# main.net
KiCad netlist of a schematic drawn in Altium Designer
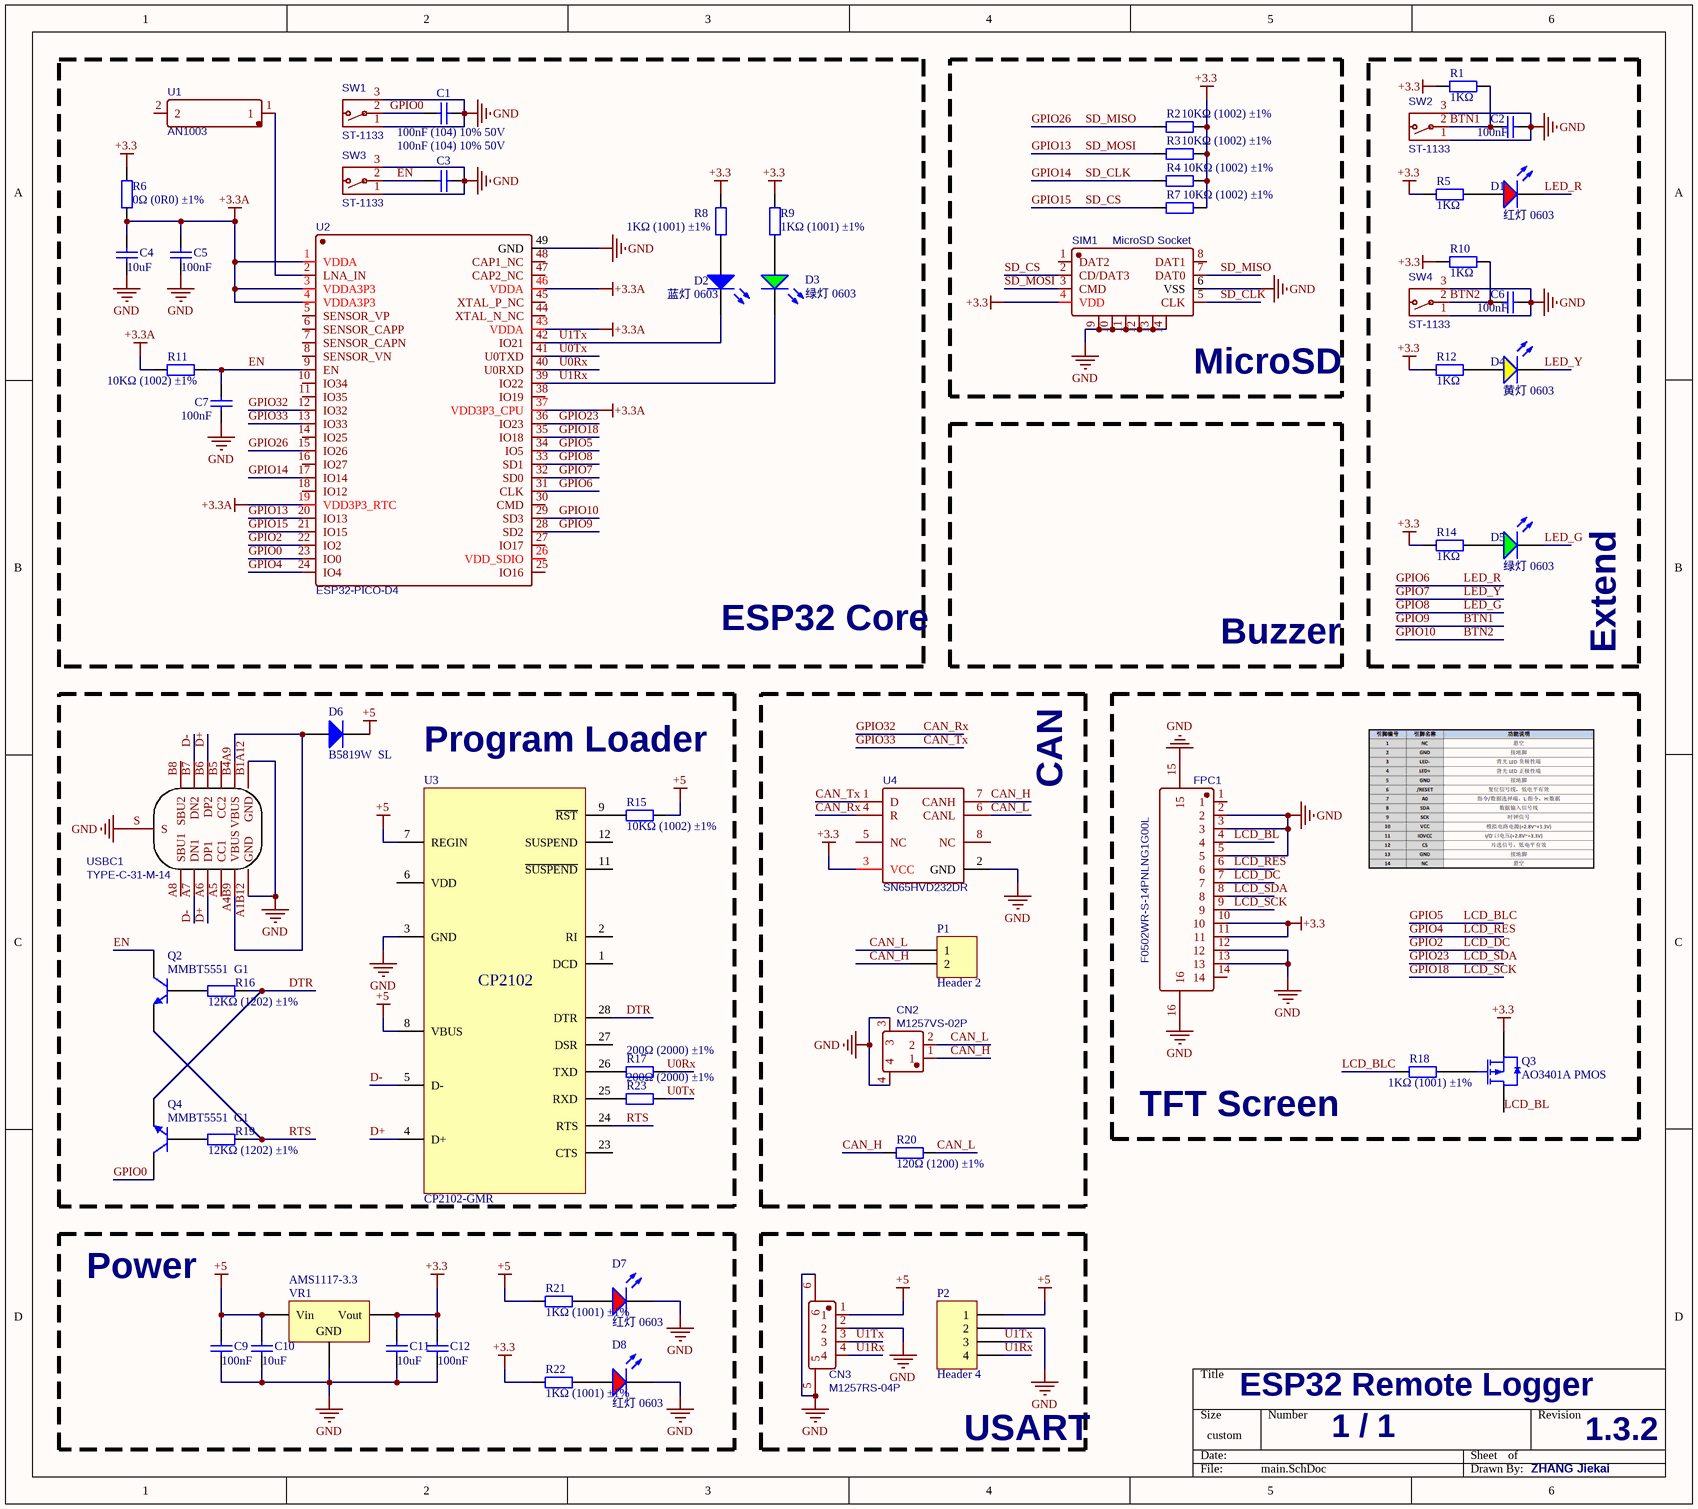
[diagram p0: main.SchDoc]

(export (version "E")
  (design (tool "Eeschema 10.0.6"))
  (components
    (comp (ref "C1")
      (value "100nF (104) 10% 50V")
      (footprint "0603_C")
      (description "贴片电容")
      (libsource (lib "Miscellaneous Devices LC") (part "0603 100nF (104) 10% 50V"))
    )
    (comp (ref "C2")
      (value "100nF")
      (footprint "0603_C")
      (description "贴片电容")
      (libsource (lib "Miscellaneous Devices LC") (part "0603 100nF (104) 10% 50V"))
    )
    (comp (ref "C3")
      (value "100nF (104) 10% 50V")
      (footprint "0603_C")
      (description "贴片电容")
      (libsource (lib "Miscellaneous Devices LC") (part "0603 100nF (104) 10% 50V"))
    )
    (comp (ref "C4")
      (value "10uF")
      (footprint "0603_C")
      (description "贴片电容")
      (libsource (lib "Miscellaneous Devices LC") (part "0603 10uF (106) 10% 10V"))
    )
    (comp (ref "C5")
      (value "100nF")
      (footprint "0603_C")
      (description "贴片电容")
      (libsource (lib "Miscellaneous Devices LC") (part "0603 100nF (104) 10% 50V"))
    )
    (comp (ref "C6")
      (value "100nF")
      (footprint "0603_C")
      (description "贴片电容")
      (libsource (lib "Miscellaneous Devices LC") (part "0603 100nF (104) 10% 50V"))
    )
    (comp (ref "C7")
      (value "100nF")
      (footprint "0603_C")
      (description "贴片电容")
      (libsource (lib "Miscellaneous Devices LC") (part "0603 100nF (104) 10% 50V"))
    )
    (comp (ref "C9")
      (value "100nF")
      (footprint "0603_C")
      (description "贴片电容")
      (libsource (lib "Miscellaneous Devices LC") (part "0603 100nF (104) 10% 50V"))
    )
    (comp (ref "C10")
      (value "10uF")
      (footprint "0603_C")
      (description "贴片电容")
      (libsource (lib "Miscellaneous Devices LC") (part "0603 10uF (106) 10% 10V"))
    )
    (comp (ref "C11")
      (value "10uF")
      (footprint "0603_C")
      (description "贴片电容")
      (libsource (lib "Miscellaneous Devices LC") (part "0603 10uF (106) 10% 10V"))
    )
    (comp (ref "C12")
      (value "100nF")
      (footprint "0603_C")
      (description "贴片电容")
      (libsource (lib "Miscellaneous Devices LC") (part "0603 100nF (104) 10% 50V"))
    )
    (comp (ref "CN2")
      (value "M1257VS-02P")
      (footprint "CONN-SMD_P1.25_M1257VS-02P")
      (fields (field (name "BOM_SUPPLIER PART") "C541819") (field (name "CONTRIBUTOR") "LCSC"))
      (libsource (lib "GH2P_Stand") (part "M1257VS-02P"))
    )
    (comp (ref "CN3")
      (value "M1257RS-04P")
      (footprint "CONN-SMD_M1257RS-04P")
      (fields (field (name "BOM_SUPPLIER PART") "C541828") (field (name "CONTRIBUTOR") "LCSC"))
      (libsource (lib "GH-lay-4P") (part "M1257RS-04P"))
    )
    (comp (ref "D1")
      (value "红灯 0603")
      (footprint "0603_LED_S1")
      (description "发光二极管")
      (libsource (lib "Miscellaneous Devices LC") (part "0603 红灯"))
    )
    (comp (ref "D2")
      (value "蓝灯 0603")
      (footprint "0603_LED_S1")
      (description "发光二极管")
      (libsource (lib "Miscellaneous Devices LC") (part "0603 蓝灯"))
    )
    (comp (ref "D3")
      (value "绿灯 0603")
      (footprint "0603_LED_S1")
      (description "发光二极管")
      (libsource (lib "Miscellaneous Devices LC") (part "0603 绿灯"))
    )
    (comp (ref "D4")
      (value "黄灯 0603")
      (footprint "0603_LED_S1")
      (description "发光二极管")
      (libsource (lib "Miscellaneous Devices LC") (part "0603 黄灯"))
    )
    (comp (ref "D5")
      (value "绿灯 0603")
      (footprint "0603_LED_S1")
      (description "发光二极管")
      (libsource (lib "Miscellaneous Devices LC") (part "0603 绿灯"))
    )
    (comp (ref "D6")
      (value "B5819W  SL")
      (footprint "SOD-123")
      (description "肖特基二极管")
      (libsource (lib "Miscellaneous Devices LC") (part "SOD-123 B5819W  SL"))
    )
    (comp (ref "D7")
      (value "红灯 0603")
      (footprint "0603_LED_S1")
      (description "发光二极管")
      (libsource (lib "Miscellaneous Devices LC") (part "0603 红灯"))
    )
    (comp (ref "D8")
      (value "红灯 0603")
      (footprint "0603_LED_S1")
      (description "发光二极管")
      (libsource (lib "Miscellaneous Devices LC") (part "0603 红灯"))
    )
    (comp (ref "FPC1")
      (value "F0502WR-S-14PNLNG1G00L")
      (footprint "FPC-SMD_P0.50-14P_F0500WR-S")
      (fields (field (name "BOM_SUPPLIER PART") "C247902") (field (name "CONTRIBUTOR") "LCSC"))
      (libsource (lib "14P-FFC-Connector") (part "F0502WR-S-14PNLNG1G00L"))
    )
    (comp (ref "P1")
      (value "Header 2")
      (footprint "HDR1X2")
      (description "Header, 2-Pin")
      (fields (field (name "PUBLISHER") "Altium Limited"))
      (libsource (lib "Miscellaneous Connectors") (part "Header 2"))
    )
    (comp (ref "P2")
      (value "Header 4")
      (footprint "HDR1X4")
      (description "Header, 4-Pin")
      (fields (field (name "PUBLISHER") "Altium Limited"))
      (libsource (lib "Miscellaneous Connectors") (part "Header 4"))
    )
    (comp (ref "Q2")
      (value "MMBT5551  G1")
      (footprint "SOT-23(SOT-23-3)")
      (description "三极管")
      (libsource (lib "Miscellaneous Devices LC") (part "SOT-23 MMBT5551  G1"))
    )
    (comp (ref "Q3")
      (value "AO3401A PMOS")
      (footprint "SOT-23-3L")
      (description "MOS(场效应管)")
      (libsource (lib "Miscellaneous Devices LC") (part "AO3401A P道沟 X13A15 SOT-23"))
    )
    (comp (ref "Q4")
      (value "MMBT5551  G1")
      (footprint "SOT-23(SOT-23-3)")
      (description "三极管")
      (libsource (lib "Miscellaneous Devices LC") (part "SOT-23 MMBT5551  G1"))
    )
    (comp (ref "R1")
      (value "1KΩ")
      (footprint "0603_R")
      (description "贴片电阻")
      (libsource (lib "Miscellaneous Devices LC") (part "0603 1KΩ (1001) 1%"))
    )
    (comp (ref "R2")
      (value "10KΩ (1002) ±1%")
      (footprint "0603_R")
      (description "贴片电阻")
      (libsource (lib "Miscellaneous Devices LC") (part "0603 10KΩ (1002) 1%"))
    )
    (comp (ref "R3")
      (value "10KΩ (1002) ±1%")
      (footprint "0603_R")
      (description "贴片电阻")
      (libsource (lib "Miscellaneous Devices LC") (part "0603 10KΩ (1002) 1%"))
    )
    (comp (ref "R4")
      (value "10KΩ (1002) ±1%")
      (footprint "0603_R")
      (description "贴片电阻")
      (libsource (lib "Miscellaneous Devices LC") (part "0603 10KΩ (1002) 1%"))
    )
    (comp (ref "R5")
      (value "1KΩ")
      (footprint "0603_R")
      (description "贴片电阻")
      (libsource (lib "Miscellaneous Devices LC") (part "0603 1KΩ (1001) 1%"))
    )
    (comp (ref "R6")
      (value "0Ω (0R0) ±1%")
      (footprint "0603_R")
      (description "贴片电阻")
      (libsource (lib "Miscellaneous Devices LC") (part "0603 0Ω (0R0) 1%"))
    )
    (comp (ref "R7")
      (value "10KΩ (1002) ±1%")
      (footprint "0603_R")
      (description "贴片电阻")
      (libsource (lib "Miscellaneous Devices LC") (part "0603 10KΩ (1002) 1%"))
    )
    (comp (ref "R8")
      (value "1KΩ (1001) ±1%")
      (footprint "0603_R")
      (description "贴片电阻")
      (libsource (lib "") (part "0603 1KΩ (1001) 1%_1"))
    )
    (comp (ref "R9")
      (value "1KΩ (1001) ±1%")
      (footprint "0603_R")
      (description "贴片电阻")
      (libsource (lib "") (part "0603 1KΩ (1001) 1%_1"))
    )
    (comp (ref "R10")
      (value "1KΩ")
      (footprint "0603_R")
      (description "贴片电阻")
      (libsource (lib "Miscellaneous Devices LC") (part "0603 1KΩ (1001) 1%"))
    )
    (comp (ref "R11")
      (value "10KΩ (1002) ±1%")
      (footprint "0603_R")
      (description "贴片电阻")
      (libsource (lib "Miscellaneous Devices LC") (part "0603 10KΩ (1002) 1%"))
    )
    (comp (ref "R12")
      (value "1KΩ")
      (footprint "0603_R")
      (description "贴片电阻")
      (libsource (lib "Miscellaneous Devices LC") (part "0603 1KΩ (1001) 1%"))
    )
    (comp (ref "R14")
      (value "1KΩ")
      (footprint "0603_R")
      (description "贴片电阻")
      (libsource (lib "Miscellaneous Devices LC") (part "0603 1KΩ (1001) 1%"))
    )
    (comp (ref "R15")
      (value "10KΩ (1002) ±1%")
      (footprint "0603_R")
      (description "贴片电阻")
      (libsource (lib "Miscellaneous Devices LC") (part "0603 10KΩ (1002) 1%"))
    )
    (comp (ref "R16")
      (value "12KΩ (1202) ±1%")
      (footprint "0603_R")
      (description "贴片电阻")
      (libsource (lib "Miscellaneous Devices LC") (part "0603 12KΩ (1202) 1%"))
    )
    (comp (ref "R17")
      (value "200Ω (2000) ±1%")
      (footprint "0603_R")
      (description "贴片电阻")
      (libsource (lib "Miscellaneous Devices LC") (part "0603 200Ω (2000) 1%"))
    )
    (comp (ref "R18")
      (value "1KΩ (1001) ±1%")
      (footprint "0603_R")
      (description "贴片电阻")
      (libsource (lib "") (part "0603 1KΩ (1001) 1%_2"))
    )
    (comp (ref "R19")
      (value "12KΩ (1202) ±1%")
      (footprint "0603_R")
      (description "贴片电阻")
      (libsource (lib "Miscellaneous Devices LC") (part "0603 12KΩ (1202) 1%"))
    )
    (comp (ref "R20")
      (value "120Ω (1200) ±1%")
      (footprint "0603_R")
      (description "贴片电阻")
      (libsource (lib "Miscellaneous Devices LC") (part "0603 120Ω (1200) 1%"))
    )
    (comp (ref "R21")
      (value "1KΩ (1001) ±1%")
      (footprint "0603_R")
      (description "贴片电阻")
      (libsource (lib "") (part "0603 1KΩ (1001) 1%_2"))
    )
    (comp (ref "R22")
      (value "1KΩ (1001) ±1%")
      (footprint "0603_R")
      (description "贴片电阻")
      (libsource (lib "") (part "0603 1KΩ (1001) 1%_2"))
    )
    (comp (ref "R23")
      (value "200Ω (2000) ±1%")
      (footprint "0603_R")
      (description "贴片电阻")
      (libsource (lib "Miscellaneous Devices LC") (part "0603 200Ω (2000) 1%"))
    )
    (comp (ref "SIM1")
      (value "MicroSD Socket")
      (footprint "SIM-SMD_8P-1040310811")
      (fields
        (field (name "BOM_SUPPLIER PART") "C585350")
        (field (name "BOM_MANUFACTURER PART") "1040310811")
        (field (name "CONTRIBUTOR") "LCSC")
      )
      (libsource (lib "MicroSD-Socket") (part "1040310811"))
    )
    (comp (ref "SW1")
      (value "ST-1133")
      (footprint "KEY-SMD_ST-1133")
      (fields (field (name "BOM_SUPPLIER PART") "C589182") (field (name "CONTRIBUTOR") "LCSC"))
      (libsource (lib "Switch-C589182") (part "ST-1133"))
    )
    (comp (ref "SW2")
      (value "ST-1133")
      (footprint "KEY-SMD_ST-1133")
      (fields (field (name "BOM_SUPPLIER PART") "C589182") (field (name "CONTRIBUTOR") "LCSC"))
      (libsource (lib "Switch-C589182") (part "ST-1133"))
    )
    (comp (ref "SW3")
      (value "ST-1133")
      (footprint "KEY-SMD_ST-1133")
      (fields (field (name "BOM_SUPPLIER PART") "C589182") (field (name "CONTRIBUTOR") "LCSC"))
      (libsource (lib "Switch-C589182") (part "ST-1133"))
    )
    (comp (ref "SW4")
      (value "ST-1133")
      (footprint "KEY-SMD_ST-1133")
      (fields (field (name "BOM_SUPPLIER PART") "C589182") (field (name "CONTRIBUTOR") "LCSC"))
      (libsource (lib "Switch-C589182") (part "ST-1133"))
    )
    (comp (ref "U1")
      (value "AN1003")
      (footprint "ANT-SMD_L10.3-W3.0")
      (fields (field (name "BOM_SUPPLIER PART") "C239240") (field (name "CONTRIBUTOR") "LCSC"))
      (libsource (lib "AN1003") (part "AN1003"))
    )
    (comp (ref "U2")
      (value "ESP32-PICO-D4")
      (footprint "QFN-48_L7.0-W7.0-P0.50-BL-EP5.4")
      (fields (field (name "BOM_SUPPLIER PART") "C193707") (field (name "CONTRIBUTOR") "LCSC"))
      (libsource (lib "ESP32-PICO-D4") (part "ESP32-PICO-D4"))
    )
    (comp (ref "U3")
      (value "CP2102-GMR")
      (footprint "QFN-28_5x5x05P")
      (description "USB")
      (libsource (lib "Miscellaneous Devices LC") (part "CP2102-GMR_[C6568]"))
    )
    (comp (ref "U4")
      (value "SN65HVD232DR")
      (footprint "SOIC-8_L5.0-W4.0-P1.27-LS6.0-BL")
      (fields (field (name "BOM_SUPPLIER PART") "C30530"))
      (libsource (lib "SN65HVD232DR") (part "SN65HVD232DR"))
    )
    (comp (ref "USBC1")
      (value "TYPE-C-31-M-14")
      (footprint "USB-C-SMD_12P-P0.50-H-F_TYPE-C-31-M-14")
      (fields (field (name "BOM_SUPPLIER PART") "C223907") (field (name "CONTRIBUTOR") "LCSC"))
      (libsource (lib "Type-C") (part "TYPE-C-31-M-14"))
    )
    (comp (ref "VR1")
      (value "AMS1117-3.3")
      (footprint "SOT-223")
      (description "低压差线性稳压(LDO)")
      (libsource (lib "Miscellaneous Devices LC") (part "SOT-223 AMS1117-3.3"))
    )
  )
  (nets
    (net (code "1") (name "+3.3") (class "Default")
      (node (ref "C11") (pin "2") (pinfunction "2_2") (pintype "passive"))
      (node (ref "C12") (pin "2") (pinfunction "2_2") (pintype "passive"))
      (node (ref "FPC1") (pin "10") (pinfunction "10_10") (pintype "passive"))
      (node (ref "FPC1") (pin "11") (pinfunction "11_11") (pintype "passive"))
      (node (ref "Q3") (pin "2") (pinfunction "S_2") (pintype "passive"))
      (node (ref "R1") (pin "2") (pinfunction "2_2") (pintype "passive"))
      (node (ref "R10") (pin "2") (pinfunction "2_2") (pintype "passive"))
      (node (ref "R12") (pin "2") (pinfunction "2_2") (pintype "passive"))
      (node (ref "R14") (pin "2") (pinfunction "2_2") (pintype "passive"))
      (node (ref "R2") (pin "2") (pinfunction "2_2") (pintype "passive"))
      (node (ref "R22") (pin "1") (pinfunction "1_1") (pintype "passive"))
      (node (ref "R3") (pin "2") (pinfunction "2_2") (pintype "passive"))
      (node (ref "R4") (pin "2") (pinfunction "2_2") (pintype "passive"))
      (node (ref "R5") (pin "2") (pinfunction "2_2") (pintype "passive"))
      (node (ref "R6") (pin "2") (pinfunction "2_2") (pintype "passive"))
      (node (ref "R7") (pin "2") (pinfunction "2_2") (pintype "passive"))
      (node (ref "R8") (pin "2") (pinfunction "2_2") (pintype "passive"))
      (node (ref "R9") (pin "2") (pinfunction "2_2") (pintype "passive"))
      (node (ref "SIM1") (pin "4") (pinfunction "VDD_4") (pintype "passive"))
      (node (ref "U4") (pin "3") (pinfunction "VCC_3") (pintype "passive"))
      (node (ref "VR1") (pin "2") (pinfunction "Vout_2") (pintype "passive"))
    )
    (net (code "2") (name "+3.3A") (class "Default")
      (node (ref "C4") (pin "2") (pinfunction "2_2") (pintype "passive"))
      (node (ref "C5") (pin "2") (pinfunction "2_2") (pintype "passive"))
      (node (ref "R11") (pin "1") (pinfunction "1_1") (pintype "passive"))
      (node (ref "R6") (pin "1") (pinfunction "1_1") (pintype "passive"))
      (node (ref "U2") (pin "1") (pinfunction "VDDA_1") (pintype "passive"))
      (node (ref "U2") (pin "19") (pinfunction "VDD3P3_RTC_19") (pintype "passive"))
      (node (ref "U2") (pin "3") (pinfunction "VDDA3P3_3") (pintype "passive"))
      (node (ref "U2") (pin "37") (pinfunction "VDD3P3_CPU_37") (pintype "passive"))
      (node (ref "U2") (pin "4") (pinfunction "VDDA3P3_4") (pintype "passive"))
      (node (ref "U2") (pin "43") (pinfunction "VDDA_43") (pintype "passive"))
      (node (ref "U2") (pin "46") (pinfunction "VDDA_46") (pintype "passive"))
    )
    (net (code "3") (name "+5") (class "Default")
      (node (ref "C10") (pin "2") (pinfunction "2_2") (pintype "passive"))
      (node (ref "C9") (pin "2") (pinfunction "2_2") (pintype "passive"))
      (node (ref "CN3") (pin "1") (pinfunction "1_1") (pintype "passive"))
      (node (ref "D6") (pin "2") (pinfunction "K_2") (pintype "passive"))
      (node (ref "P2") (pin "1") (pinfunction "1_1") (pintype "passive"))
      (node (ref "R15") (pin "2") (pinfunction "2_2") (pintype "passive"))
      (node (ref "R21") (pin "1") (pinfunction "1_1") (pintype "passive"))
      (node (ref "U3") (pin "7") (pinfunction "REGIN_7") (pintype "passive"))
      (node (ref "U3") (pin "8") (pinfunction "VBUS_8") (pintype "passive"))
      (node (ref "VR1") (pin "3") (pinfunction "Vin_3") (pintype "passive"))
    )
    (net (code "4") (name "/BTN1") (class "Default")
      (node (ref "C2") (pin "1") (pinfunction "1_1") (pintype "passive"))
      (node (ref "R1") (pin "1") (pinfunction "1_1") (pintype "passive"))
      (node (ref "SW2") (pin "2") (pinfunction "2_2") (pintype "passive"))
      (node (ref "U2") (pin "28") (pinfunction "SD2_28") (pintype "passive"))
    )
    (net (code "5") (name "/BTN2") (class "Default")
      (node (ref "C6") (pin "1") (pinfunction "1_1") (pintype "passive"))
      (node (ref "R10") (pin "1") (pinfunction "1_1") (pintype "passive"))
      (node (ref "SW4") (pin "2") (pinfunction "2_2") (pintype "passive"))
      (node (ref "U2") (pin "29") (pinfunction "SD3_29") (pintype "passive"))
    )
    (net (code "6") (name "/CAN_H") (class "Default")
      (node (ref "CN2") (pin "1") (pinfunction "1_1") (pintype "passive"))
      (node (ref "P1") (pin "2") (pinfunction "2_2") (pintype "passive"))
      (node (ref "R20") (pin "1") (pinfunction "1_1") (pintype "passive"))
      (node (ref "U4") (pin "7") (pinfunction "CANH_7") (pintype "passive"))
    )
    (net (code "7") (name "/CAN_L") (class "Default")
      (node (ref "CN2") (pin "2") (pinfunction "2_2") (pintype "passive"))
      (node (ref "P1") (pin "1") (pinfunction "1_1") (pintype "passive"))
      (node (ref "R20") (pin "2") (pinfunction "2_2") (pintype "passive"))
      (node (ref "U4") (pin "6") (pinfunction "CANL_6") (pintype "passive"))
    )
    (net (code "8") (name "/CAN_Rx") (class "Default")
      (node (ref "U2") (pin "12") (pinfunction "IO32_12") (pintype "passive"))
      (node (ref "U4") (pin "4") (pinfunction "R_4") (pintype "passive"))
    )
    (net (code "9") (name "/CAN_Tx") (class "Default")
      (node (ref "U2") (pin "13") (pinfunction "IO33_13") (pintype "passive"))
      (node (ref "U4") (pin "1") (pinfunction "D_1") (pintype "passive"))
    )
    (net (code "10") (name "/D+") (class "Default")
      (node (ref "U3") (pin "4") (pinfunction "D+_4") (pintype "passive"))
      (node (ref "USBC1") (pin "A6") (pinfunction "DP1_A6") (pintype "passive"))
      (node (ref "USBC1") (pin "B6") (pinfunction "DP2_B6") (pintype "passive"))
    )
    (net (code "11") (name "/D-") (class "Default")
      (node (ref "U3") (pin "5") (pinfunction "D-_5") (pintype "passive"))
      (node (ref "USBC1") (pin "A7") (pinfunction "DN1_A7") (pintype "passive"))
      (node (ref "USBC1") (pin "B7") (pinfunction "DN2_B7") (pintype "passive"))
    )
    (net (code "12") (name "/DTR") (class "Default")
      (node (ref "Q4") (pin "2") (pinfunction "E_2") (pintype "passive"))
      (node (ref "R16") (pin "2") (pinfunction "2_2") (pintype "passive"))
      (node (ref "U3") (pin "28") (pinfunction "DTR_28") (pintype "passive"))
    )
    (net (code "13") (name "/EN") (class "Default")
      (node (ref "C3") (pin "1") (pinfunction "1_1") (pintype "passive"))
      (node (ref "C7") (pin "2") (pinfunction "2_2") (pintype "passive"))
      (node (ref "Q2") (pin "3") (pinfunction "C_3") (pintype "passive"))
      (node (ref "R11") (pin "2") (pinfunction "2_2") (pintype "passive"))
      (node (ref "SW3") (pin "2") (pinfunction "2_2") (pintype "passive"))
      (node (ref "U2") (pin "9") (pinfunction "EN_9") (pintype "passive"))
    )
    (net (code "14") (name "/GPIO0") (class "Default")
      (node (ref "C1") (pin "1") (pinfunction "1_1") (pintype "passive"))
      (node (ref "Q4") (pin "3") (pinfunction "C_3") (pintype "passive"))
      (node (ref "SW1") (pin "2") (pinfunction "2_2") (pintype "passive"))
      (node (ref "U2") (pin "23") (pinfunction "IO0_23") (pintype "passive"))
    )
    (net (code "15") (name "/GPIO2") (class "Default")
      (node (ref "FPC1") (pin "7") (pinfunction "7_7") (pintype "passive"))
      (node (ref "U2") (pin "22") (pinfunction "IO2_22") (pintype "passive"))
    )
    (net (code "16") (name "/GPIO4") (class "Default")
      (node (ref "FPC1") (pin "6") (pinfunction "6_6") (pintype "passive"))
      (node (ref "U2") (pin "24") (pinfunction "IO4_24") (pintype "passive"))
    )
    (net (code "17") (name "/GPIO5") (class "Default")
      (node (ref "R18") (pin "1") (pinfunction "1_1") (pintype "passive"))
      (node (ref "U2") (pin "34") (pinfunction "IO5_34") (pintype "passive"))
    )
    (net (code "18") (name "/GPIO6") (class "Default")
      (node (ref "D1") (pin "K") (pinfunction "K_K") (pintype "passive"))
      (node (ref "U2") (pin "31") (pinfunction "CLK_31") (pintype "passive"))
    )
    (net (code "19") (name "/GPIO7") (class "Default")
      (node (ref "D4") (pin "K") (pinfunction "K_K") (pintype "passive"))
      (node (ref "U2") (pin "32") (pinfunction "SD0_32") (pintype "passive"))
    )
    (net (code "20") (name "/GPIO8") (class "Default")
      (node (ref "D5") (pin "K") (pinfunction "K_K") (pintype "passive"))
      (node (ref "U2") (pin "33") (pinfunction "SD1_33") (pintype "passive"))
    )
    (net (code "21") (name "/GPIO13") (class "Default")
      (node (ref "R3") (pin "1") (pinfunction "1_1") (pintype "passive"))
      (node (ref "SIM1") (pin "3") (pinfunction "CMD_3") (pintype "passive"))
      (node (ref "U2") (pin "20") (pinfunction "IO13_20") (pintype "passive"))
    )
    (net (code "22") (name "/GPIO14") (class "Default")
      (node (ref "R4") (pin "1") (pinfunction "1_1") (pintype "passive"))
      (node (ref "SIM1") (pin "5") (pinfunction "CLK_5") (pintype "passive"))
      (node (ref "U2") (pin "17") (pinfunction "IO14_17") (pintype "passive"))
    )
    (net (code "23") (name "/GPIO15") (class "Default")
      (node (ref "R7") (pin "1") (pinfunction "1_1") (pintype "passive"))
      (node (ref "SIM1") (pin "2") (pinfunction "CD/DAT3_2") (pintype "passive"))
      (node (ref "U2") (pin "21") (pinfunction "IO15_21") (pintype "passive"))
    )
    (net (code "24") (name "/GPIO18") (class "Default")
      (node (ref "FPC1") (pin "9") (pinfunction "9_9") (pintype "passive"))
      (node (ref "U2") (pin "35") (pinfunction "IO18_35") (pintype "passive"))
    )
    (net (code "25") (name "/GPIO23") (class "Default")
      (node (ref "FPC1") (pin "8") (pinfunction "8_8") (pintype "passive"))
      (node (ref "U2") (pin "36") (pinfunction "IO23_36") (pintype "passive"))
    )
    (net (code "26") (name "/GPIO26") (class "Default")
      (node (ref "R2") (pin "1") (pinfunction "1_1") (pintype "passive"))
      (node (ref "SIM1") (pin "7") (pinfunction "DAT0_7") (pintype "passive"))
      (node (ref "U2") (pin "15") (pinfunction "IO26_15") (pintype "passive"))
    )
    (net (code "27") (name "/LCD_BL") (class "Default")
      (node (ref "FPC1") (pin "4") (pinfunction "4_4") (pintype "passive"))
      (node (ref "Q3") (pin "3") (pinfunction "D_3") (pintype "passive"))
    )
    (net (code "28") (name "/RTS") (class "Default")
      (node (ref "Q2") (pin "2") (pinfunction "E_2") (pintype "passive"))
      (node (ref "R19") (pin "2") (pinfunction "2_2") (pintype "passive"))
      (node (ref "U3") (pin "24") (pinfunction "RTS_24") (pintype "passive"))
    )
    (net (code "29") (name "/U0Rx") (class "Default")
      (node (ref "R17") (pin "2") (pinfunction "2_2") (pintype "passive"))
      (node (ref "U2") (pin "40") (pinfunction "U0RXD_40") (pintype "passive"))
    )
    (net (code "30") (name "/U0Tx") (class "Default")
      (node (ref "R23") (pin "2") (pinfunction "2_2") (pintype "passive"))
      (node (ref "U2") (pin "41") (pinfunction "U0TXD_41") (pintype "passive"))
    )
    (net (code "31") (name "/U1Rx") (class "Default")
      (node (ref "CN3") (pin "4") (pinfunction "4_4") (pintype "passive"))
      (node (ref "D3") (pin "K") (pinfunction "K_K") (pintype "passive"))
      (node (ref "P2") (pin "4") (pinfunction "4_4") (pintype "passive"))
      (node (ref "U2") (pin "39") (pinfunction "IO22_39") (pintype "passive"))
    )
    (net (code "32") (name "/U1Tx") (class "Default")
      (node (ref "CN3") (pin "3") (pinfunction "3_3") (pintype "passive"))
      (node (ref "D2") (pin "K") (pinfunction "K_K") (pintype "passive"))
      (node (ref "P2") (pin "3") (pinfunction "3_3") (pintype "passive"))
      (node (ref "U2") (pin "42") (pinfunction "IO21_42") (pintype "passive"))
    )
    (net (code "33") (name "GND") (class "Default")
      (node (ref "C1") (pin "2") (pinfunction "2_2") (pintype "passive"))
      (node (ref "C10") (pin "1") (pinfunction "1_1") (pintype "passive"))
      (node (ref "C11") (pin "1") (pinfunction "1_1") (pintype "passive"))
      (node (ref "C12") (pin "1") (pinfunction "1_1") (pintype "passive"))
      (node (ref "C2") (pin "2") (pinfunction "2_2") (pintype "passive"))
      (node (ref "C3") (pin "2") (pinfunction "2_2") (pintype "passive"))
      (node (ref "C4") (pin "1") (pinfunction "1_1") (pintype "passive"))
      (node (ref "C5") (pin "1") (pinfunction "1_1") (pintype "passive"))
      (node (ref "C6") (pin "2") (pinfunction "2_2") (pintype "passive"))
      (node (ref "C7") (pin "1") (pinfunction "1_1") (pintype "passive"))
      (node (ref "C9") (pin "1") (pinfunction "1_1") (pintype "passive"))
      (node (ref "CN2") (pin "3") (pinfunction "3_3") (pintype "passive"))
      (node (ref "CN2") (pin "4") (pinfunction "4_4") (pintype "passive"))
      (node (ref "CN3") (pin "2") (pinfunction "2_2") (pintype "passive"))
      (node (ref "CN3") (pin "5") (pinfunction "5_5") (pintype "passive"))
      (node (ref "CN3") (pin "6") (pinfunction "6_6") (pintype "passive"))
      (node (ref "D7") (pin "K") (pinfunction "K_K") (pintype "passive"))
      (node (ref "D8") (pin "K") (pinfunction "K_K") (pintype "passive"))
      (node (ref "FPC1") (pin "12") (pinfunction "12_12") (pintype "passive"))
      (node (ref "FPC1") (pin "13") (pinfunction "13_13") (pintype "passive"))
      (node (ref "FPC1") (pin "15") (pinfunction "15_15") (pintype "passive"))
      (node (ref "FPC1") (pin "16") (pinfunction "16_16") (pintype "passive"))
      (node (ref "FPC1") (pin "2") (pinfunction "2_2") (pintype "passive"))
      (node (ref "FPC1") (pin "3") (pinfunction "3_3") (pintype "passive"))
      (node (ref "FPC1") (pin "5") (pinfunction "5_5") (pintype "passive"))
      (node (ref "P2") (pin "2") (pinfunction "2_2") (pintype "passive"))
      (node (ref "SIM1") (pin "10") (pinfunction "10_10") (pintype "passive"))
      (node (ref "SIM1") (pin "11") (pinfunction "11_11") (pintype "passive"))
      (node (ref "SIM1") (pin "12") (pinfunction "12_12") (pintype "passive"))
      (node (ref "SIM1") (pin "13") (pinfunction "13_13") (pintype "passive"))
      (node (ref "SIM1") (pin "14") (pinfunction "14_14") (pintype "passive"))
      (node (ref "SIM1") (pin "6") (pinfunction "VSS_6") (pintype "passive"))
      (node (ref "SIM1") (pin "9") (pinfunction "9_9") (pintype "passive"))
      (node (ref "SW1") (pin "1") (pinfunction "1_1") (pintype "passive"))
      (node (ref "SW1") (pin "3") (pinfunction "3_3") (pintype "passive"))
      (node (ref "SW2") (pin "1") (pinfunction "1_1") (pintype "passive"))
      (node (ref "SW2") (pin "3") (pinfunction "3_3") (pintype "passive"))
      (node (ref "SW3") (pin "1") (pinfunction "1_1") (pintype "passive"))
      (node (ref "SW3") (pin "3") (pinfunction "3_3") (pintype "passive"))
      (node (ref "SW4") (pin "1") (pinfunction "1_1") (pintype "passive"))
      (node (ref "SW4") (pin "3") (pinfunction "3_3") (pintype "passive"))
      (node (ref "U2") (pin "49") (pinfunction "GND_49") (pintype "passive"))
      (node (ref "U3") (pin "3") (pinfunction "GND_3") (pintype "passive"))
      (node (ref "U4") (pin "2") (pinfunction "GND_2") (pintype "passive"))
      (node (ref "USBC1") (pin "A1B12") (pinfunction "GND_A1B12") (pintype "passive"))
      (node (ref "USBC1") (pin "B1A12") (pinfunction "GND_B1A12") (pintype "passive"))
      (node (ref "USBC1") (pin "S") (pinfunction "S_S") (pintype "passive"))
      (node (ref "VR1") (pin "1") (pinfunction "GND_1") (pintype "passive"))
    )
    (net (code "34") (name "Net-(D1-PadA)") (class "Default")
      (node (ref "D1") (pin "A") (pinfunction "A_A") (pintype "passive"))
      (node (ref "R5") (pin "1") (pinfunction "1_1") (pintype "passive"))
    )
    (net (code "35") (name "Net-(D2-PadA)") (class "Default")
      (node (ref "D2") (pin "A") (pinfunction "A_A") (pintype "passive"))
      (node (ref "R8") (pin "1") (pinfunction "1_1") (pintype "passive"))
    )
    (net (code "36") (name "Net-(D3-PadA)") (class "Default")
      (node (ref "D3") (pin "A") (pinfunction "A_A") (pintype "passive"))
      (node (ref "R9") (pin "1") (pinfunction "1_1") (pintype "passive"))
    )
    (net (code "37") (name "Net-(D4-PadA)") (class "Default")
      (node (ref "D4") (pin "A") (pinfunction "A_A") (pintype "passive"))
      (node (ref "R12") (pin "1") (pinfunction "1_1") (pintype "passive"))
    )
    (net (code "38") (name "Net-(D5-PadA)") (class "Default")
      (node (ref "D5") (pin "A") (pinfunction "A_A") (pintype "passive"))
      (node (ref "R14") (pin "1") (pinfunction "1_1") (pintype "passive"))
    )
    (net (code "39") (name "Net-(D6-A)") (class "Default")
      (node (ref "D6") (pin "1") (pinfunction "A_1") (pintype "passive"))
      (node (ref "USBC1") (pin "A4B9") (pinfunction "VBUS_A4B9") (pintype "passive"))
      (node (ref "USBC1") (pin "B4A9") (pinfunction "VBUS_B4A9") (pintype "passive"))
    )
    (net (code "40") (name "Net-(D7-PadA)") (class "Default")
      (node (ref "D7") (pin "A") (pinfunction "A_A") (pintype "passive"))
      (node (ref "R21") (pin "2") (pinfunction "2_2") (pintype "passive"))
    )
    (net (code "41") (name "Net-(D8-PadA)") (class "Default")
      (node (ref "D8") (pin "A") (pinfunction "A_A") (pintype "passive"))
      (node (ref "R22") (pin "2") (pinfunction "2_2") (pintype "passive"))
    )
    (net (code "42") (name "Net-(Q2-B)") (class "Default")
      (node (ref "Q2") (pin "1") (pinfunction "B_1") (pintype "passive"))
      (node (ref "R16") (pin "1") (pinfunction "1_1") (pintype "passive"))
    )
    (net (code "43") (name "Net-(Q3-G)") (class "Default")
      (node (ref "Q3") (pin "1") (pinfunction "G_1") (pintype "passive"))
      (node (ref "R18") (pin "2") (pinfunction "2_2") (pintype "passive"))
    )
    (net (code "44") (name "Net-(Q4-B)") (class "Default")
      (node (ref "Q4") (pin "1") (pinfunction "B_1") (pintype "passive"))
      (node (ref "R19") (pin "1") (pinfunction "1_1") (pintype "passive"))
    )
    (net (code "45") (name "Net-(U2-LNA_IN)") (class "Default")
      (node (ref "U1") (pin "1") (pinfunction "1_1") (pintype "passive"))
      (node (ref "U2") (pin "2") (pinfunction "LNA_IN_2") (pintype "passive"))
    )
    (net (code "46") (name "Net-(U3-RXD)") (class "Default")
      (node (ref "R23") (pin "1") (pinfunction "1_1") (pintype "passive"))
      (node (ref "U3") (pin "25") (pinfunction "RXD_25") (pintype "passive"))
    )
    (net (code "47") (name "Net-(U3-TXD)") (class "Default")
      (node (ref "R17") (pin "1") (pinfunction "1_1") (pintype "passive"))
      (node (ref "U3") (pin "26") (pinfunction "TXD_26") (pintype "passive"))
    )
    (net (code "48") (name "Net-(U3-~{RST})") (class "Default")
      (node (ref "R15") (pin "1") (pinfunction "1_1") (pintype "passive"))
      (node (ref "U3") (pin "9") (pinfunction "~{RST}_9") (pintype "passive"))
    )
    (net (code "49") (name "unconnected-(FPC1-Pad1)") (class "Default")
      (node (ref "FPC1") (pin "1") (pinfunction "1_1") (pintype "passive"))
    )
    (net (code "50") (name "unconnected-(FPC1-Pad14)") (class "Default")
      (node (ref "FPC1") (pin "14") (pinfunction "14_14") (pintype "passive"))
    )
    (net (code "51") (name "unconnected-(SIM1-DAT1-Pad8)") (class "Default")
      (node (ref "SIM1") (pin "8") (pinfunction "DAT1_8") (pintype "passive"))
    )
    (net (code "52") (name "unconnected-(SIM1-DAT2-Pad1)") (class "Default")
      (node (ref "SIM1") (pin "1") (pinfunction "DAT2_1") (pintype "passive"))
    )
    (net (code "53") (name "unconnected-(U1-Pad2)") (class "Default")
      (node (ref "U1") (pin "2") (pinfunction "2_2") (pintype "passive"))
    )
    (net (code "54") (name "unconnected-(U2-CAP1_NC-Pad48)") (class "Default")
      (node (ref "U2") (pin "48") (pinfunction "CAP1_NC_48") (pintype "passive"))
    )
    (net (code "55") (name "unconnected-(U2-CAP2_NC-Pad47)") (class "Default")
      (node (ref "U2") (pin "47") (pinfunction "CAP2_NC_47") (pintype "passive"))
    )
    (net (code "56") (name "unconnected-(U2-CMD-Pad30)") (class "Default")
      (node (ref "U2") (pin "30") (pinfunction "CMD_30") (pintype "passive"))
    )
    (net (code "57") (name "unconnected-(U2-IO12-Pad18)") (class "Default")
      (node (ref "U2") (pin "18") (pinfunction "IO12_18") (pintype "passive"))
    )
    (net (code "58") (name "unconnected-(U2-IO16-Pad25)") (class "Default")
      (node (ref "U2") (pin "25") (pinfunction "IO16_25") (pintype "passive"))
    )
    (net (code "59") (name "unconnected-(U2-IO17-Pad27)") (class "Default")
      (node (ref "U2") (pin "27") (pinfunction "IO17_27") (pintype "passive"))
    )
    (net (code "60") (name "unconnected-(U2-IO19-Pad38)") (class "Default")
      (node (ref "U2") (pin "38") (pinfunction "IO19_38") (pintype "passive"))
    )
    (net (code "61") (name "unconnected-(U2-IO25-Pad14)") (class "Default")
      (node (ref "U2") (pin "14") (pinfunction "IO25_14") (pintype "passive"))
    )
    (net (code "62") (name "unconnected-(U2-IO27-Pad16)") (class "Default")
      (node (ref "U2") (pin "16") (pinfunction "IO27_16") (pintype "passive"))
    )
    (net (code "63") (name "unconnected-(U2-IO34-Pad10)") (class "Default")
      (node (ref "U2") (pin "10") (pinfunction "IO34_10") (pintype "passive"))
    )
    (net (code "64") (name "unconnected-(U2-IO35-Pad11)") (class "Default")
      (node (ref "U2") (pin "11") (pinfunction "IO35_11") (pintype "passive"))
    )
    (net (code "65") (name "unconnected-(U2-SENSOR_CAPN-Pad7)") (class "Default")
      (node (ref "U2") (pin "7") (pinfunction "SENSOR_CAPN_7") (pintype "passive"))
    )
    (net (code "66") (name "unconnected-(U2-SENSOR_CAPP-Pad6)") (class "Default")
      (node (ref "U2") (pin "6") (pinfunction "SENSOR_CAPP_6") (pintype "passive"))
    )
    (net (code "67") (name "unconnected-(U2-SENSOR_VN-Pad8)") (class "Default")
      (node (ref "U2") (pin "8") (pinfunction "SENSOR_VN_8") (pintype "passive"))
    )
    (net (code "68") (name "unconnected-(U2-SENSOR_VP-Pad5)") (class "Default")
      (node (ref "U2") (pin "5") (pinfunction "SENSOR_VP_5") (pintype "passive"))
    )
    (net (code "69") (name "unconnected-(U2-VDD_SDIO-Pad26)") (class "Default")
      (node (ref "U2") (pin "26") (pinfunction "VDD_SDIO_26") (pintype "passive"))
    )
    (net (code "70") (name "unconnected-(U2-XTAL_N_NC-Pad44)") (class "Default")
      (node (ref "U2") (pin "44") (pinfunction "XTAL_N_NC_44") (pintype "passive"))
    )
    (net (code "71") (name "unconnected-(U2-XTAL_P_NC-Pad45)") (class "Default")
      (node (ref "U2") (pin "45") (pinfunction "XTAL_P_NC_45") (pintype "passive"))
    )
    (net (code "72") (name "unconnected-(U3-CTS-Pad23)") (class "Default")
      (node (ref "U3") (pin "23") (pinfunction "CTS_23") (pintype "passive"))
    )
    (net (code "73") (name "unconnected-(U3-DCD-Pad1)") (class "Default")
      (node (ref "U3") (pin "1") (pinfunction "DCD_1") (pintype "passive"))
    )
    (net (code "74") (name "unconnected-(U3-DSR-Pad27)") (class "Default")
      (node (ref "U3") (pin "27") (pinfunction "DSR_27") (pintype "passive"))
    )
    (net (code "75") (name "unconnected-(U3-RI-Pad2)") (class "Default")
      (node (ref "U3") (pin "2") (pinfunction "RI_2") (pintype "passive"))
    )
    (net (code "76") (name "unconnected-(U3-SUSPEND-Pad12)") (class "Default")
      (node (ref "U3") (pin "12") (pinfunction "SUSPEND_12") (pintype "passive"))
    )
    (net (code "77") (name "unconnected-(U3-VDD-Pad6)") (class "Default")
      (node (ref "U3") (pin "6") (pinfunction "VDD_6") (pintype "passive"))
    )
    (net (code "78") (name "unconnected-(U3-~{SUSPEND}-Pad11)") (class "Default")
      (node (ref "U3") (pin "11") (pinfunction "~{SUSPEND}_11") (pintype "passive"))
    )
    (net (code "79") (name "unconnected-(U4-NC-Pad5)") (class "Default")
      (node (ref "U4") (pin "5") (pinfunction "NC_5") (pintype "passive"))
    )
    (net (code "80") (name "unconnected-(U4-NC-Pad8)") (class "Default")
      (node (ref "U4") (pin "8") (pinfunction "NC_8") (pintype "passive"))
    )
    (net (code "81") (name "unconnected-(USBC1-CC1-PadA5)") (class "Default")
      (node (ref "USBC1") (pin "A5") (pinfunction "CC1_A5") (pintype "passive"))
    )
    (net (code "82") (name "unconnected-(USBC1-CC2-PadB5)") (class "Default")
      (node (ref "USBC1") (pin "B5") (pinfunction "CC2_B5") (pintype "passive"))
    )
    (net (code "83") (name "unconnected-(USBC1-SBU1-PadA8)") (class "Default")
      (node (ref "USBC1") (pin "A8") (pinfunction "SBU1_A8") (pintype "passive"))
    )
    (net (code "84") (name "unconnected-(USBC1-SBU2-PadB8)") (class "Default")
      (node (ref "USBC1") (pin "B8") (pinfunction "SBU2_B8") (pintype "passive"))
    )
  )
)
